# Moisture.net
KiCad netlist of a schematic drawn in Altium Designer
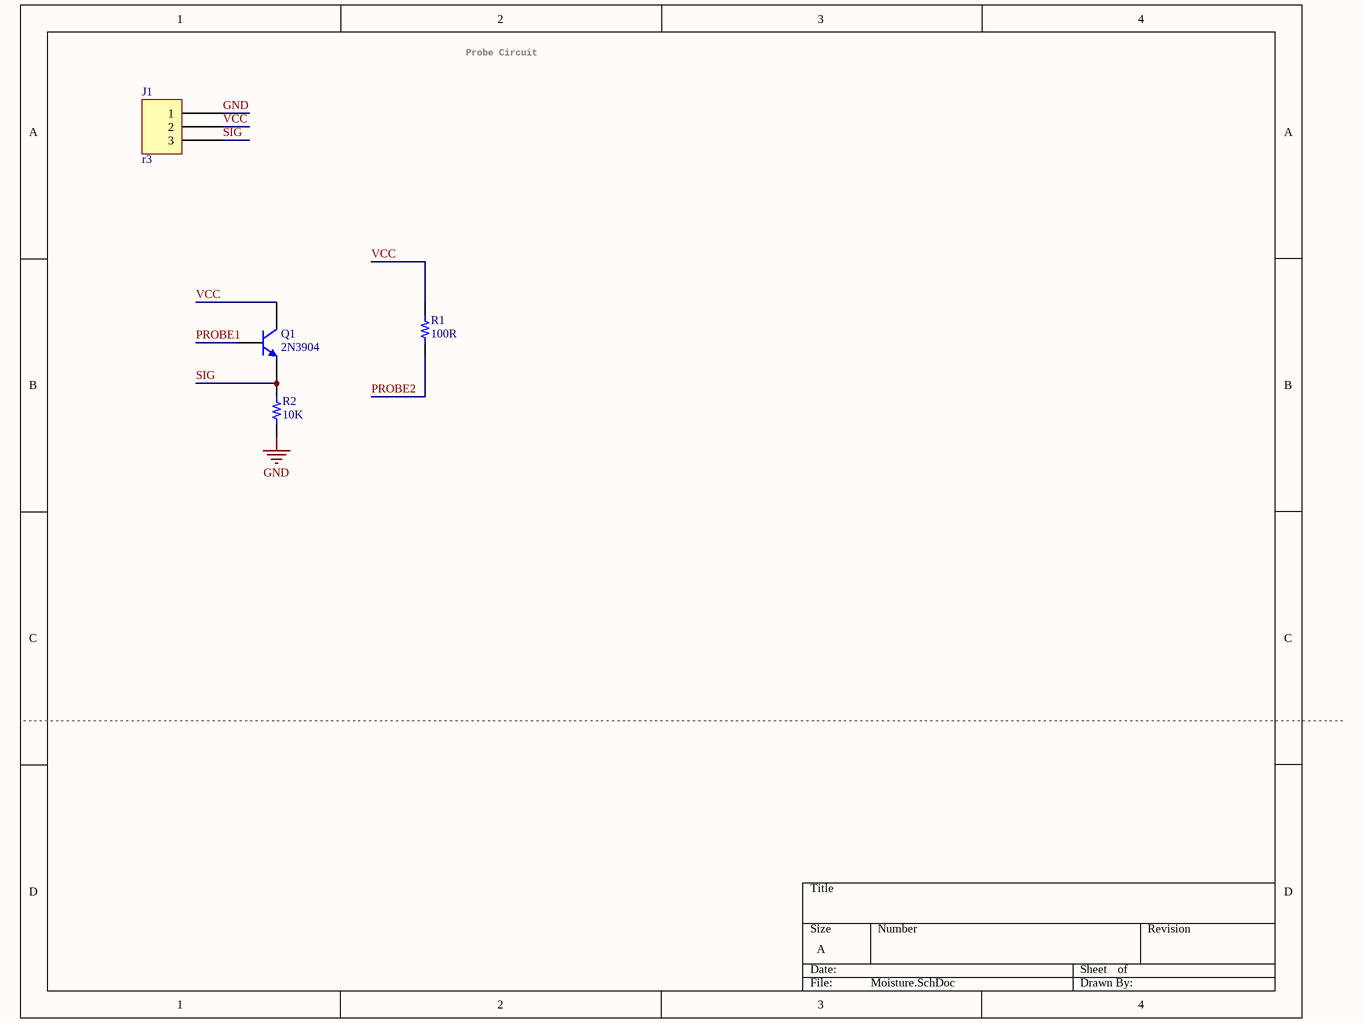
[diagram p0: Moisture.SchDoc]

(export (version "E")
  (design (tool "Eeschema 10.0.6"))
  (components
    (comp (ref "J1")
      (value "r3")
      (footprint "MOLEX SDA-70553-3PIN")
      (libsource (lib "Connectors") (part "r3"))
    )
    (comp (ref "Q1")
      (value "2N3904")
      (footprint "SOT23")
      (description "NPN")
      (fields (field (name "E-MAIL") "picpars@gmail.com"))
      (libsource (lib "Other") (part "2N2222"))
    )
    (comp (ref "R1")
      (value "100R")
      (footprint "RES 1206/3216")
      (description "SMT Resistor")
      (libsource (lib "Cap_Res") (part "Resistor"))
    )
    (comp (ref "R2")
      (value "10K")
      (footprint "RES 1206/3216")
      (description "SMT Resistor")
      (libsource (lib "Cap_Res") (part "Resistor"))
    )
  )
  (nets
    (net (code "1") (name "/PROBE1") (class "Default")
      (node (ref "Q1") (pin "B") (pinfunction "B_B") (pintype "passive"))
    )
    (net (code "2") (name "/PROBE2") (class "Default")
      (node (ref "R1") (pin "1") (pinfunction "1_1") (pintype "passive"))
    )
    (net (code "3") (name "/SIG") (class "Default")
      (node (ref "J1") (pin "3") (pinfunction "3_3") (pintype "passive"))
      (node (ref "Q1") (pin "E") (pinfunction "E_E") (pintype "passive"))
      (node (ref "R2") (pin "2") (pinfunction "2_2") (pintype "passive"))
    )
    (net (code "4") (name "/VCC") (class "Default")
      (node (ref "J1") (pin "2") (pinfunction "2_2") (pintype "passive"))
      (node (ref "Q1") (pin "C") (pinfunction "C_C") (pintype "passive"))
      (node (ref "R1") (pin "2") (pinfunction "2_2") (pintype "passive"))
    )
    (net (code "5") (name "GND") (class "Default")
      (node (ref "J1") (pin "1") (pinfunction "1_1") (pintype "passive"))
      (node (ref "R2") (pin "1") (pinfunction "1_1") (pintype "passive"))
    )
  )
)
